# DiffInput.net
KiCad netlist of a schematic drawn in Altium Designer
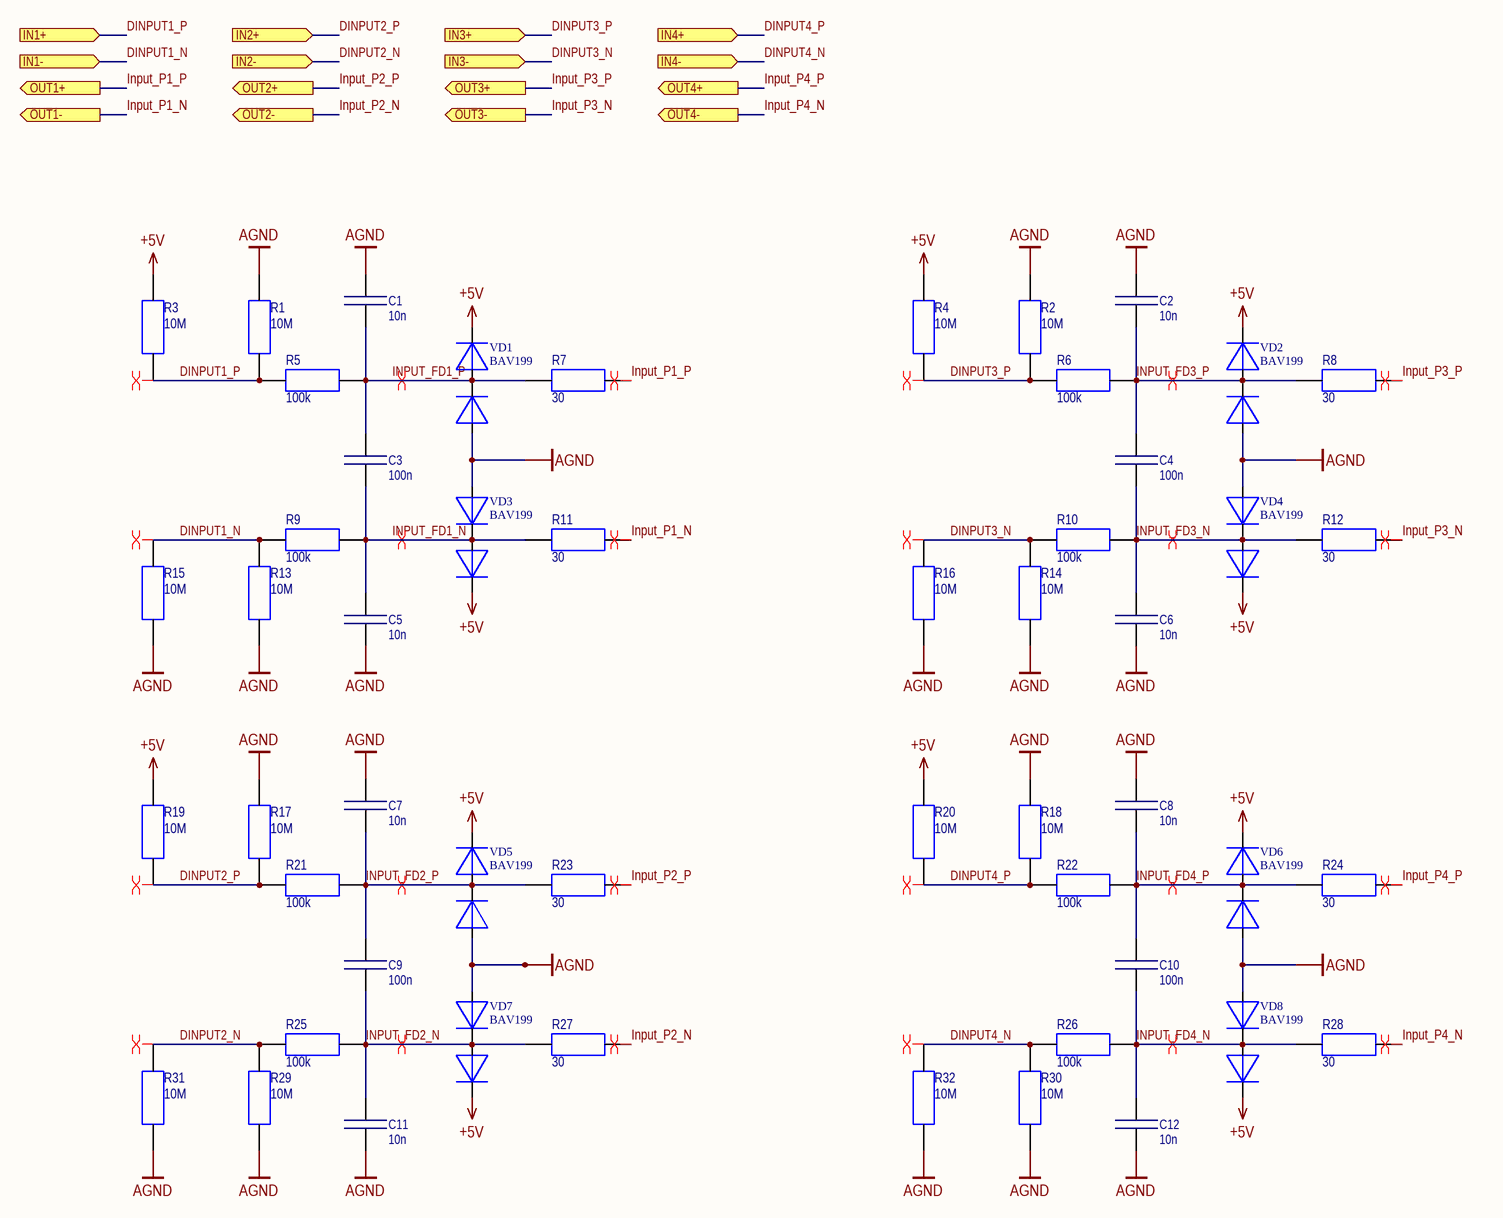
[diagram p0: DiffInput.SchDoc]

(export (version "E")
  (design (tool "Eeschema 10.0.6"))
  (components
    (comp (ref "C1")
      (value "10n")
      (footprint "SMDRC0805")
      (description "Generic capasitor non-polar")
      (fields (field (name "PARTNUMBER") "Capacitor 0805 10n"))
      (libsource (lib "library") (part "Capacitor"))
    )
    (comp (ref "C2")
      (value "10n")
      (footprint "SMDRC0805")
      (description "Generic capasitor non-polar")
      (fields (field (name "PARTNUMBER") "Capacitor 0805 10n"))
      (libsource (lib "library") (part "Capacitor"))
    )
    (comp (ref "C3")
      (value "100n")
      (footprint "SMDRC0805")
      (description "Generic capasitor non-polar")
      (fields (field (name "PARTNUMBER") "Capacitor 0805 100n"))
      (libsource (lib "library") (part "Capacitor"))
    )
    (comp (ref "C4")
      (value "100n")
      (footprint "SMDRC0805")
      (description "Generic capasitor non-polar")
      (fields (field (name "PARTNUMBER") "Capacitor 0805 100n"))
      (libsource (lib "library") (part "Capacitor"))
    )
    (comp (ref "C5")
      (value "10n")
      (footprint "SMDRC0805")
      (description "Generic capasitor non-polar")
      (fields (field (name "PARTNUMBER") "Capacitor 0805 10n"))
      (libsource (lib "library") (part "Capacitor"))
    )
    (comp (ref "C6")
      (value "10n")
      (footprint "SMDRC0805")
      (description "Generic capasitor non-polar")
      (fields (field (name "PARTNUMBER") "Capacitor 0805 10n"))
      (libsource (lib "library") (part "Capacitor"))
    )
    (comp (ref "C7")
      (value "10n")
      (footprint "SMDRC0805")
      (description "Generic capasitor non-polar")
      (fields (field (name "PARTNUMBER") "Capacitor 0805 10n"))
      (libsource (lib "library") (part "Capacitor"))
    )
    (comp (ref "C8")
      (value "10n")
      (footprint "SMDRC0805")
      (description "Generic capasitor non-polar")
      (fields (field (name "PARTNUMBER") "Capacitor 0805 10n"))
      (libsource (lib "library") (part "Capacitor"))
    )
    (comp (ref "C9")
      (value "100n")
      (footprint "SMDRC0805")
      (description "Generic capasitor non-polar")
      (fields (field (name "PARTNUMBER") "Capacitor 0805 100n"))
      (libsource (lib "library") (part "Capacitor"))
    )
    (comp (ref "C10")
      (value "100n")
      (footprint "SMDRC0805")
      (description "Generic capasitor non-polar")
      (fields (field (name "PARTNUMBER") "Capacitor 0805 100n"))
      (libsource (lib "library") (part "Capacitor"))
    )
    (comp (ref "C11")
      (value "10n")
      (footprint "SMDRC0805")
      (description "Generic capasitor non-polar")
      (fields (field (name "PARTNUMBER") "Capacitor 0805 10n"))
      (libsource (lib "library") (part "Capacitor"))
    )
    (comp (ref "C12")
      (value "10n")
      (footprint "SMDRC0805")
      (description "Generic capasitor non-polar")
      (fields (field (name "PARTNUMBER") "Capacitor 0805 10n"))
      (libsource (lib "library") (part "Capacitor"))
    )
    (comp (ref "R1")
      (value "10M")
      (footprint "SMDRC0805")
      (description "Generic resistor")
      (fields (field (name "PARTNUMBER") "Resistor 0805 10M"))
      (libsource (lib "library") (part "Resistor"))
    )
    (comp (ref "R2")
      (value "10M")
      (footprint "SMDRC0805")
      (description "Generic resistor")
      (fields (field (name "PARTNUMBER") "Resistor 0805 10M"))
      (libsource (lib "library") (part "Resistor"))
    )
    (comp (ref "R3")
      (value "10M")
      (footprint "SMDRC0805")
      (description "Generic resistor")
      (fields (field (name "PARTNUMBER") "Resistor 0805 10M"))
      (libsource (lib "library") (part "Resistor"))
    )
    (comp (ref "R4")
      (value "10M")
      (footprint "SMDRC0805")
      (description "Generic resistor")
      (fields (field (name "PARTNUMBER") "Resistor 0805 10M"))
      (libsource (lib "library") (part "Resistor"))
    )
    (comp (ref "R5")
      (value "100k")
      (footprint "SMDRC0805")
      (description "Generic resistor")
      (fields (field (name "PARTNUMBER") "Resistor 0805 100k"))
      (libsource (lib "library") (part "Resistor"))
    )
    (comp (ref "R6")
      (value "100k")
      (footprint "SMDRC0805")
      (description "Generic resistor")
      (fields (field (name "PARTNUMBER") "Resistor 0805 100k"))
      (libsource (lib "library") (part "Resistor"))
    )
    (comp (ref "R7")
      (value "30")
      (footprint "SMDRC0805")
      (description "Generic resistor")
      (fields (field (name "PARTNUMBER") "Resistor 0805 30"))
      (libsource (lib "") (part "Resistor_1"))
    )
    (comp (ref "R8")
      (value "30")
      (footprint "SMDRC0805")
      (description "Generic resistor")
      (fields (field (name "PARTNUMBER") "Resistor 0805 30"))
      (libsource (lib "") (part "Resistor_1"))
    )
    (comp (ref "R9")
      (value "100k")
      (footprint "SMDRC0805")
      (description "Generic resistor")
      (fields (field (name "PARTNUMBER") "Resistor 0805 100k"))
      (libsource (lib "library") (part "Resistor"))
    )
    (comp (ref "R10")
      (value "100k")
      (footprint "SMDRC0805")
      (description "Generic resistor")
      (fields (field (name "PARTNUMBER") "Resistor 0805 100k"))
      (libsource (lib "library") (part "Resistor"))
    )
    (comp (ref "R11")
      (value "30")
      (footprint "SMDRC0805")
      (description "Generic resistor")
      (fields (field (name "PARTNUMBER") "Resistor 0805 30"))
      (libsource (lib "") (part "Resistor_1"))
    )
    (comp (ref "R12")
      (value "30")
      (footprint "SMDRC0805")
      (description "Generic resistor")
      (fields (field (name "PARTNUMBER") "Resistor 0805 30"))
      (libsource (lib "") (part "Resistor_1"))
    )
    (comp (ref "R13")
      (value "10M")
      (footprint "SMDRC0805")
      (description "Generic resistor")
      (fields (field (name "PARTNUMBER") "Resistor 0805 10M"))
      (libsource (lib "library") (part "Resistor"))
    )
    (comp (ref "R14")
      (value "10M")
      (footprint "SMDRC0805")
      (description "Generic resistor")
      (fields (field (name "PARTNUMBER") "Resistor 0805 10M"))
      (libsource (lib "library") (part "Resistor"))
    )
    (comp (ref "R15")
      (value "10M")
      (footprint "SMDRC0805")
      (description "Generic resistor")
      (fields (field (name "PARTNUMBER") "Resistor 0805 10M"))
      (libsource (lib "library") (part "Resistor"))
    )
    (comp (ref "R16")
      (value "10M")
      (footprint "SMDRC0805")
      (description "Generic resistor")
      (fields (field (name "PARTNUMBER") "Resistor 0805 10M"))
      (libsource (lib "library") (part "Resistor"))
    )
    (comp (ref "R17")
      (value "10M")
      (footprint "SMDRC0805")
      (description "Generic resistor")
      (fields (field (name "PARTNUMBER") "Resistor 0805 10M"))
      (libsource (lib "library") (part "Resistor"))
    )
    (comp (ref "R18")
      (value "10M")
      (footprint "SMDRC0805")
      (description "Generic resistor")
      (fields (field (name "PARTNUMBER") "Resistor 0805 10M"))
      (libsource (lib "library") (part "Resistor"))
    )
    (comp (ref "R19")
      (value "10M")
      (footprint "SMDRC0805")
      (description "Generic resistor")
      (fields (field (name "PARTNUMBER") "Resistor 0805 10M"))
      (libsource (lib "library") (part "Resistor"))
    )
    (comp (ref "R20")
      (value "10M")
      (footprint "SMDRC0805")
      (description "Generic resistor")
      (fields (field (name "PARTNUMBER") "Resistor 0805 10M"))
      (libsource (lib "library") (part "Resistor"))
    )
    (comp (ref "R21")
      (value "100k")
      (footprint "SMDRC0805")
      (description "Generic resistor")
      (fields (field (name "PARTNUMBER") "Resistor 0805 100k"))
      (libsource (lib "library") (part "Resistor"))
    )
    (comp (ref "R22")
      (value "100k")
      (footprint "SMDRC0805")
      (description "Generic resistor")
      (fields (field (name "PARTNUMBER") "Resistor 0805 100k"))
      (libsource (lib "library") (part "Resistor"))
    )
    (comp (ref "R23")
      (value "30")
      (footprint "SMDRC0805")
      (description "Generic resistor")
      (fields (field (name "PARTNUMBER") "Resistor 0805 30"))
      (libsource (lib "") (part "Resistor_1"))
    )
    (comp (ref "R24")
      (value "30")
      (footprint "SMDRC0805")
      (description "Generic resistor")
      (fields (field (name "PARTNUMBER") "Resistor 0805 30"))
      (libsource (lib "") (part "Resistor_1"))
    )
    (comp (ref "R25")
      (value "100k")
      (footprint "SMDRC0805")
      (description "Generic resistor")
      (fields (field (name "PARTNUMBER") "Resistor 0805 100k"))
      (libsource (lib "library") (part "Resistor"))
    )
    (comp (ref "R26")
      (value "100k")
      (footprint "SMDRC0805")
      (description "Generic resistor")
      (fields (field (name "PARTNUMBER") "Resistor 0805 100k"))
      (libsource (lib "library") (part "Resistor"))
    )
    (comp (ref "R27")
      (value "30")
      (footprint "SMDRC0805")
      (description "Generic resistor")
      (fields (field (name "PARTNUMBER") "Resistor 0805 30"))
      (libsource (lib "") (part "Resistor_1"))
    )
    (comp (ref "R28")
      (value "30")
      (footprint "SMDRC0805")
      (description "Generic resistor")
      (fields (field (name "PARTNUMBER") "Resistor 0805 30"))
      (libsource (lib "") (part "Resistor_1"))
    )
    (comp (ref "R29")
      (value "10M")
      (footprint "SMDRC0805")
      (description "Generic resistor")
      (fields (field (name "PARTNUMBER") "Resistor 0805 10M"))
      (libsource (lib "library") (part "Resistor"))
    )
    (comp (ref "R30")
      (value "10M")
      (footprint "SMDRC0805")
      (description "Generic resistor")
      (fields (field (name "PARTNUMBER") "Resistor 0805 10M"))
      (libsource (lib "library") (part "Resistor"))
    )
    (comp (ref "R31")
      (value "10M")
      (footprint "SMDRC0805")
      (description "Generic resistor")
      (fields (field (name "PARTNUMBER") "Resistor 0805 10M"))
      (libsource (lib "library") (part "Resistor"))
    )
    (comp (ref "R32")
      (value "10M")
      (footprint "SMDRC0805")
      (description "Generic resistor")
      (fields (field (name "PARTNUMBER") "Resistor 0805 10M"))
      (libsource (lib "library") (part "Resistor"))
    )
    (comp (ref "VD1")
      (value "BAV199")
      (footprint "Standard:SOT23 (TO-236AB)")
      (fields (field (name "MANUFACTURER") "NXP"))
      (libsource (lib "Diod") (part "BAV199"))
    )
    (comp (ref "VD2")
      (value "BAV199")
      (footprint "Standard:SOT23 (TO-236AB)")
      (fields (field (name "MANUFACTURER") "NXP"))
      (libsource (lib "Diod") (part "BAV199"))
    )
    (comp (ref "VD3")
      (value "BAV199")
      (footprint "Standard:SOT23 (TO-236AB)")
      (fields (field (name "MANUFACTURER") "NXP"))
      (libsource (lib "Diod") (part "BAV199"))
    )
    (comp (ref "VD4")
      (value "BAV199")
      (footprint "Standard:SOT23 (TO-236AB)")
      (fields (field (name "MANUFACTURER") "NXP"))
      (libsource (lib "Diod") (part "BAV199"))
    )
    (comp (ref "VD5")
      (value "BAV199")
      (footprint "Standard:SOT23 (TO-236AB)")
      (fields (field (name "MANUFACTURER") "NXP"))
      (libsource (lib "Diod") (part "BAV199"))
    )
    (comp (ref "VD6")
      (value "BAV199")
      (footprint "Standard:SOT23 (TO-236AB)")
      (fields (field (name "MANUFACTURER") "NXP"))
      (libsource (lib "Diod") (part "BAV199"))
    )
    (comp (ref "VD7")
      (value "BAV199")
      (footprint "Standard:SOT23 (TO-236AB)")
      (fields (field (name "MANUFACTURER") "NXP"))
      (libsource (lib "Diod") (part "BAV199"))
    )
    (comp (ref "VD8")
      (value "BAV199")
      (footprint "Standard:SOT23 (TO-236AB)")
      (fields (field (name "MANUFACTURER") "NXP"))
      (libsource (lib "Diod") (part "BAV199"))
    )
  )
  (nets
    (net (code "1") (name "+5V") (class "Default")
      (node (ref "R19") (pin "2") (pinfunction "2_2") (pintype "passive"))
      (node (ref "R20") (pin "2") (pinfunction "2_2") (pintype "passive"))
      (node (ref "R3") (pin "2") (pinfunction "2_2") (pintype "passive"))
      (node (ref "R4") (pin "2") (pinfunction "2_2") (pintype "passive"))
      (node (ref "VD1") (pin "2") (pinfunction "2_2") (pintype "passive"))
      (node (ref "VD2") (pin "2") (pinfunction "2_2") (pintype "passive"))
      (node (ref "VD3") (pin "2") (pinfunction "2_2") (pintype "passive"))
      (node (ref "VD4") (pin "2") (pinfunction "2_2") (pintype "passive"))
      (node (ref "VD5") (pin "2") (pinfunction "2_2") (pintype "passive"))
      (node (ref "VD6") (pin "2") (pinfunction "2_2") (pintype "passive"))
      (node (ref "VD7") (pin "2") (pinfunction "2_2") (pintype "passive"))
      (node (ref "VD8") (pin "2") (pinfunction "2_2") (pintype "passive"))
    )
    (net (code "2") (name "/DINPUT1_N") (class "Default")
      (node (ref "R13") (pin "2") (pinfunction "2_2") (pintype "passive"))
      (node (ref "R15") (pin "2") (pinfunction "2_2") (pintype "passive"))
      (node (ref "R9") (pin "1") (pinfunction "1_1") (pintype "passive"))
    )
    (net (code "3") (name "/DINPUT1_P") (class "Default")
      (node (ref "R1") (pin "1") (pinfunction "1_1") (pintype "passive"))
      (node (ref "R3") (pin "1") (pinfunction "1_1") (pintype "passive"))
      (node (ref "R5") (pin "1") (pinfunction "1_1") (pintype "passive"))
    )
    (net (code "4") (name "/DINPUT2_N") (class "Default")
      (node (ref "R25") (pin "1") (pinfunction "1_1") (pintype "passive"))
      (node (ref "R29") (pin "2") (pinfunction "2_2") (pintype "passive"))
      (node (ref "R31") (pin "2") (pinfunction "2_2") (pintype "passive"))
    )
    (net (code "5") (name "/DINPUT2_P") (class "Default")
      (node (ref "R17") (pin "1") (pinfunction "1_1") (pintype "passive"))
      (node (ref "R19") (pin "1") (pinfunction "1_1") (pintype "passive"))
      (node (ref "R21") (pin "1") (pinfunction "1_1") (pintype "passive"))
    )
    (net (code "6") (name "/DINPUT3_N") (class "Default")
      (node (ref "R10") (pin "1") (pinfunction "1_1") (pintype "passive"))
      (node (ref "R14") (pin "2") (pinfunction "2_2") (pintype "passive"))
      (node (ref "R16") (pin "2") (pinfunction "2_2") (pintype "passive"))
    )
    (net (code "7") (name "/DINPUT3_P") (class "Default")
      (node (ref "R2") (pin "1") (pinfunction "1_1") (pintype "passive"))
      (node (ref "R4") (pin "1") (pinfunction "1_1") (pintype "passive"))
      (node (ref "R6") (pin "1") (pinfunction "1_1") (pintype "passive"))
    )
    (net (code "8") (name "/DINPUT4_N") (class "Default")
      (node (ref "R26") (pin "1") (pinfunction "1_1") (pintype "passive"))
      (node (ref "R30") (pin "2") (pinfunction "2_2") (pintype "passive"))
      (node (ref "R32") (pin "2") (pinfunction "2_2") (pintype "passive"))
    )
    (net (code "9") (name "/DINPUT4_P") (class "Default")
      (node (ref "R18") (pin "1") (pinfunction "1_1") (pintype "passive"))
      (node (ref "R20") (pin "1") (pinfunction "1_1") (pintype "passive"))
      (node (ref "R22") (pin "1") (pinfunction "1_1") (pintype "passive"))
    )
    (net (code "10") (name "/INPUT_FD1_N") (class "Default")
      (node (ref "C3") (pin "1") (pintype "passive"))
      (node (ref "C5") (pin "2") (pintype "passive"))
      (node (ref "R11") (pin "1") (pinfunction "1_1") (pintype "passive"))
      (node (ref "R9") (pin "2") (pinfunction "2_2") (pintype "passive"))
      (node (ref "VD3") (pin "3") (pinfunction "3_3") (pintype "passive"))
    )
    (net (code "11") (name "/INPUT_FD1_P") (class "Default")
      (node (ref "C1") (pin "1") (pintype "passive"))
      (node (ref "C3") (pin "2") (pintype "passive"))
      (node (ref "R5") (pin "2") (pinfunction "2_2") (pintype "passive"))
      (node (ref "R7") (pin "1") (pinfunction "1_1") (pintype "passive"))
      (node (ref "VD1") (pin "3") (pinfunction "3_3") (pintype "passive"))
    )
    (net (code "12") (name "/INPUT_FD2_N") (class "Default")
      (node (ref "C11") (pin "2") (pintype "passive"))
      (node (ref "C9") (pin "1") (pintype "passive"))
      (node (ref "R25") (pin "2") (pinfunction "2_2") (pintype "passive"))
      (node (ref "R27") (pin "1") (pinfunction "1_1") (pintype "passive"))
      (node (ref "VD7") (pin "3") (pinfunction "3_3") (pintype "passive"))
    )
    (net (code "13") (name "/INPUT_FD2_P") (class "Default")
      (node (ref "C7") (pin "1") (pintype "passive"))
      (node (ref "C9") (pin "2") (pintype "passive"))
      (node (ref "R21") (pin "2") (pinfunction "2_2") (pintype "passive"))
      (node (ref "R23") (pin "1") (pinfunction "1_1") (pintype "passive"))
      (node (ref "VD5") (pin "3") (pinfunction "3_3") (pintype "passive"))
    )
    (net (code "14") (name "/INPUT_FD3_N") (class "Default")
      (node (ref "C4") (pin "1") (pintype "passive"))
      (node (ref "C6") (pin "2") (pintype "passive"))
      (node (ref "R10") (pin "2") (pinfunction "2_2") (pintype "passive"))
      (node (ref "R12") (pin "1") (pinfunction "1_1") (pintype "passive"))
      (node (ref "VD4") (pin "3") (pinfunction "3_3") (pintype "passive"))
    )
    (net (code "15") (name "/INPUT_FD3_P") (class "Default")
      (node (ref "C2") (pin "1") (pintype "passive"))
      (node (ref "C4") (pin "2") (pintype "passive"))
      (node (ref "R6") (pin "2") (pinfunction "2_2") (pintype "passive"))
      (node (ref "R8") (pin "1") (pinfunction "1_1") (pintype "passive"))
      (node (ref "VD2") (pin "3") (pinfunction "3_3") (pintype "passive"))
    )
    (net (code "16") (name "/INPUT_FD4_N") (class "Default")
      (node (ref "C10") (pin "1") (pintype "passive"))
      (node (ref "C12") (pin "2") (pintype "passive"))
      (node (ref "R26") (pin "2") (pinfunction "2_2") (pintype "passive"))
      (node (ref "R28") (pin "1") (pinfunction "1_1") (pintype "passive"))
      (node (ref "VD8") (pin "3") (pinfunction "3_3") (pintype "passive"))
    )
    (net (code "17") (name "/INPUT_FD4_P") (class "Default")
      (node (ref "C10") (pin "2") (pintype "passive"))
      (node (ref "C8") (pin "1") (pintype "passive"))
      (node (ref "R22") (pin "2") (pinfunction "2_2") (pintype "passive"))
      (node (ref "R24") (pin "1") (pinfunction "1_1") (pintype "passive"))
      (node (ref "VD6") (pin "3") (pinfunction "3_3") (pintype "passive"))
    )
    (net (code "18") (name "/Input_P1_N") (class "Default")
      (node (ref "R11") (pin "2") (pinfunction "2_2") (pintype "passive"))
    )
    (net (code "19") (name "/Input_P1_P") (class "Default")
      (node (ref "R7") (pin "2") (pinfunction "2_2") (pintype "passive"))
    )
    (net (code "20") (name "/Input_P2_N") (class "Default")
      (node (ref "R27") (pin "2") (pinfunction "2_2") (pintype "passive"))
    )
    (net (code "21") (name "/Input_P2_P") (class "Default")
      (node (ref "R23") (pin "2") (pinfunction "2_2") (pintype "passive"))
    )
    (net (code "22") (name "/Input_P3_N") (class "Default")
      (node (ref "R12") (pin "2") (pinfunction "2_2") (pintype "passive"))
    )
    (net (code "23") (name "/Input_P3_P") (class "Default")
      (node (ref "R8") (pin "2") (pinfunction "2_2") (pintype "passive"))
    )
    (net (code "24") (name "/Input_P4_N") (class "Default")
      (node (ref "R28") (pin "2") (pinfunction "2_2") (pintype "passive"))
    )
    (net (code "25") (name "/Input_P4_P") (class "Default")
      (node (ref "R24") (pin "2") (pinfunction "2_2") (pintype "passive"))
    )
    (net (code "26") (name "AGND") (class "Default")
      (node (ref "C1") (pin "2") (pintype "passive"))
      (node (ref "C11") (pin "1") (pintype "passive"))
      (node (ref "C12") (pin "1") (pintype "passive"))
      (node (ref "C2") (pin "2") (pintype "passive"))
      (node (ref "C5") (pin "1") (pintype "passive"))
      (node (ref "C6") (pin "1") (pintype "passive"))
      (node (ref "C7") (pin "2") (pintype "passive"))
      (node (ref "C8") (pin "2") (pintype "passive"))
      (node (ref "R1") (pin "2") (pinfunction "2_2") (pintype "passive"))
      (node (ref "R13") (pin "1") (pinfunction "1_1") (pintype "passive"))
      (node (ref "R14") (pin "1") (pinfunction "1_1") (pintype "passive"))
      (node (ref "R15") (pin "1") (pinfunction "1_1") (pintype "passive"))
      (node (ref "R16") (pin "1") (pinfunction "1_1") (pintype "passive"))
      (node (ref "R17") (pin "2") (pinfunction "2_2") (pintype "passive"))
      (node (ref "R18") (pin "2") (pinfunction "2_2") (pintype "passive"))
      (node (ref "R2") (pin "2") (pinfunction "2_2") (pintype "passive"))
      (node (ref "R29") (pin "1") (pinfunction "1_1") (pintype "passive"))
      (node (ref "R30") (pin "1") (pinfunction "1_1") (pintype "passive"))
      (node (ref "R31") (pin "1") (pinfunction "1_1") (pintype "passive"))
      (node (ref "R32") (pin "1") (pinfunction "1_1") (pintype "passive"))
      (node (ref "VD1") (pin "1") (pinfunction "1_1") (pintype "passive"))
      (node (ref "VD2") (pin "1") (pinfunction "1_1") (pintype "passive"))
      (node (ref "VD3") (pin "1") (pinfunction "1_1") (pintype "passive"))
      (node (ref "VD4") (pin "1") (pinfunction "1_1") (pintype "passive"))
      (node (ref "VD5") (pin "1") (pinfunction "1_1") (pintype "passive"))
      (node (ref "VD6") (pin "1") (pinfunction "1_1") (pintype "passive"))
      (node (ref "VD7") (pin "1") (pinfunction "1_1") (pintype "passive"))
      (node (ref "VD8") (pin "1") (pinfunction "1_1") (pintype "passive"))
    )
  )
)
